# QG-2864KSWEG01_OLED_Display_Module.net
KiCad netlist of a schematic drawn in Altium Designer
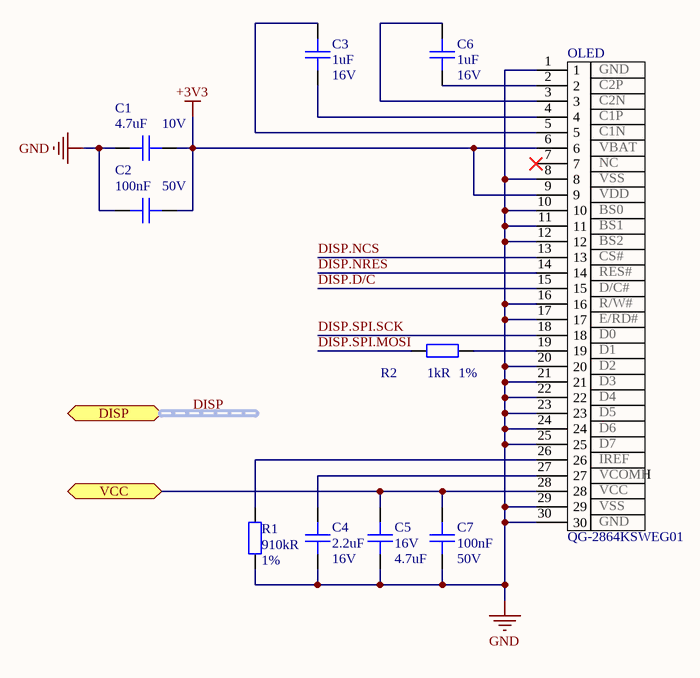
[diagram p0: QG-2864KSWEG01_OLED_Display_Module.SchDoc]

(export (version "E")
  (design (tool "Eeschema 10.0.6"))
  (components
    (comp (ref "C1")
      (value "CAP CER 4.7UF 10V X5R 0603")
      (footprint "C0603")
      (description "4.7µF ±10% 10V Ceramic Capacitor X5R 0603 (1608 Metric)")
      (fields
        (field (name "MANUFACTURER") "Yageo")
        (field (name "MANUFACTURER PART NUMBER") "CC0603KRX5R6BB475")
        (field (name "VOLTAGE RATING") "10V")
        (field (name "CAPACITANCE") "4.7uF")
      )
      (libsource (lib "capacitors_smd") (part "CAP CER 4.7UF 10V X5R 0603"))
    )
    (comp (ref "C2")
      (value "CAP CER 0.1UF 50V X7R 0402")
      (footprint "C0402")
      (description "0.1µF ±10% 50V Ceramic Capacitor X7R 0402 (1005 Metric)")
      (fields
        (field (name "MANUFACTURER PART NUMBER") "CGA2B3X7R1H104K050BB")
        (field (name "MANUFACTURER") "TDK")
        (field (name "CAPACITANCE") "100nF")
        (field (name "VOLTAGE") "50V")
      )
      (libsource (lib "capacitors_smd") (part "CAP CER 0.1UF 50V X7R 0402"))
    )
    (comp (ref "C3")
      (value "CAP CER 1UF 16V X5R 0603")
      (footprint "C0603")
      (description "1µF ±10% 16V Ceramic Capacitor X5R 0603 (1608 Metric)")
      (fields
        (field (name "MANUFACTURER") "Yageo")
        (field (name "MANUFACTURER PART NUMBER") "CC0603KRX5R7BB105")
        (field (name "CAPACITANCE") "1uF")
        (field (name "VOLTAGE RATING") "16V")
      )
      (libsource (lib "capacitors_smd") (part "CAP CER 1UF 16V X5R 0603"))
    )
    (comp (ref "C4")
      (value "CAP CER 2.2UF 16V X5R 0603")
      (footprint "C0603")
      (description "2.2µF ±10% 16V Ceramic Capacitor X5R 0603 (1608 Metric)")
      (fields
        (field (name "MANUFACTURER") "Yageo")
        (field (name "MANUFACTURER PART NUMBER") "CC0603KRX5R7BB225")
        (field (name "CAPACITANCE") "2.2uF")
        (field (name "VOLTAGE RATING") "16V")
      )
      (libsource (lib "capacitors_smd") (part "CAP CER 2.2UF 16V X5R 0603"))
    )
    (comp (ref "C5")
      (value "CAP CER 4.7UF 16V X5R 0603")
      (footprint "C0603")
      (description "4.7µF ±10% 16V Ceramic Capacitor X5R 0603 (1608 Metric)")
      (fields
        (field (name "MANUFACTURER") "Yageo")
        (field (name "MANUFACTURER PART NUMBER") "CC0603KRX5R7BB475")
        (field (name "VOLTAGE RATING") "16V")
        (field (name "CAPACITANCE") "4.7uF")
      )
      (libsource (lib "capacitors_smd") (part "CAP CER 4.7UF 16V X5R 0603"))
    )
    (comp (ref "C6")
      (value "CAP CER 1UF 16V X5R 0603")
      (footprint "C0603")
      (description "1µF ±10% 16V Ceramic Capacitor X5R 0603 (1608 Metric)")
      (fields
        (field (name "MANUFACTURER") "Yageo")
        (field (name "MANUFACTURER PART NUMBER") "CC0603KRX5R7BB105")
        (field (name "CAPACITANCE") "1uF")
        (field (name "VOLTAGE RATING") "16V")
      )
      (libsource (lib "capacitors_smd") (part "CAP CER 1UF 16V X5R 0603"))
    )
    (comp (ref "C7")
      (value "CAP CER 0.1UF 50V X7R 0402")
      (footprint "C0402")
      (description "0.1µF ±10% 50V Ceramic Capacitor X7R 0402 (1005 Metric)")
      (fields
        (field (name "MANUFACTURER PART NUMBER") "CGA2B3X7R1H104K050BB")
        (field (name "MANUFACTURER") "TDK")
        (field (name "CAPACITANCE") "100nF")
        (field (name "VOLTAGE") "50V")
      )
      (libsource (lib "capacitors_smd") (part "CAP CER 0.1UF 50V X7R 0402"))
    )
    (comp (ref "OLED")
      (value "QG-2864KSWEG01")
      (footprint "QG-2864KSWEG01_Flipped")
      (description "OLED Display Module FPC #LT1306P22 TOP 30P 0.7MM")
      (fields
        (field (name "MANUFACTURER") "Limito Technology Inc.")
        (field (name "PIN_1") "GND")
        (field (name "PIN_2") "C2P")
        (field (name "PIN_3") "C2N")
        (field (name "PIN_4") "C1P")
        (field (name "PIN_5") "C1N")
        (field (name "PIN_6") "VBAT")
        (field (name "PIN_7") "NC")
        (field (name "PIN_8") "VSS")
        (field (name "PIN_9") "VDD")
        (field (name "PIN_10") "BS0")
        (field (name "PIN_11") "BS1")
        (field (name "PIN_12") "BS2")
        (field (name "PIN_13") "CS#")
        (field (name "PIN_14") "RES#")
        (field (name "PIN_15") "D/C#")
        (field (name "PIN_16") "R/W#")
        (field (name "PIN_17") "E/RD#")
        (field (name "PIN_18") "D0")
        (field (name "PIN_19") "D1")
        (field (name "PIN_20") "D2")
        (field (name "PIN_21") "D3")
        (field (name "PIN_22") "D4")
        (field (name "PIN_23") "D5")
        (field (name "PIN_24") "D6")
        (field (name "PIN_25") "D7")
        (field (name "PIN_26") "IREF")
        (field (name "PIN_27") "VCOMH")
        (field (name "PIN_28") "VCC")
        (field (name "PIN_29") "VSS")
        (field (name "PIN_30") "GND")
      )
      (libsource (lib "BLDC_Motor_Driver") (part "MOD QG-2864KSWEG01 OLED DISPLAY"))
    )
    (comp (ref "R1")
      (value "RES SMD 910K OHM 1% 1/16W 0402")
      (footprint "R0402")
      (description "910 kOhms ±1% 0.063W, 1/16W Chip Resistor 0402 (1005 Metric) Moisture Resistant Thick Film")
      (fields
        (field (name "MANUFACTURER") "Yageo")
        (field (name "MANUFACTURER PART NUMBER") "RC0402FR-07910KL")
        (field (name "RESISTANCE") "910kR")
        (field (name "TOLERANCE") "1%")
      )
      (libsource (lib "resistors_smd") (part "RES SMD 910K OHM 1% 1/16W 0402"))
    )
    (comp (ref "R2")
      (value "RES SMD 1K OHM 1% 1/16W 0402")
      (footprint "R0402")
      (description "1 kOhms ±1% 0.063W, 1/16W Chip Resistor 0402 (1005 Metric) Moisture Resistant Thick Film")
      (fields
        (field (name "MANUFACTURER") "Yageo")
        (field (name "MANUFACTURER PART NUMBER") "RC0402FR-071KL")
        (field (name "TOLERANCE") "1%")
        (field (name "RESISTANCE") "1kR")
      )
      (libsource (lib "resistors_smd") (part "RES SMD 1K OHM 1% 1/16W 0402"))
    )
  )
  (nets
    (net (code "2") (name "+3V3") (class "Default")
      (node (ref "C1") (pin "1") (pinfunction "1_1") (pintype "passive"))
      (node (ref "C2") (pin "1") (pinfunction "1_1") (pintype "passive"))
      (node (ref "OLED") (pin "6") (pinfunction "6_6") (pintype "passive"))
      (node (ref "OLED") (pin "9") (pinfunction "9_9") (pintype "passive"))
    )
    (net (code "3") (name "/DISP.D{slash}C") (class "Default")
      (node (ref "OLED") (pin "15") (pinfunction "15_15") (pintype "passive"))
    )
    (net (code "4") (name "/DISP.NCS") (class "Default")
      (node (ref "OLED") (pin "13") (pinfunction "13_13") (pintype "passive"))
    )
    (net (code "5") (name "/DISP.NRES") (class "Default")
      (node (ref "OLED") (pin "14") (pinfunction "14_14") (pintype "passive"))
    )
    (net (code "6") (name "/DISP.SPI.MOSI") (class "Default")
      (node (ref "R2") (pin "1") (pinfunction "1_1") (pintype "passive"))
    )
    (net (code "7") (name "/DISP.SPI.SCK") (class "Default")
      (node (ref "OLED") (pin "18") (pinfunction "18_18") (pintype "passive"))
    )
    (net (code "8") (name "/VCC") (class "Default")
      (node (ref "C5") (pin "1") (pinfunction "1_1") (pintype "passive"))
      (node (ref "C7") (pin "1") (pinfunction "1_1") (pintype "passive"))
      (node (ref "OLED") (pin "28") (pinfunction "28_28") (pintype "passive"))
    )
    (net (code "10") (name "GND") (class "Default")
      (node (ref "C1") (pin "2") (pinfunction "2_2") (pintype "passive"))
      (node (ref "C2") (pin "2") (pinfunction "2_2") (pintype "passive"))
      (node (ref "C4") (pin "1") (pinfunction "1_1") (pintype "passive"))
      (node (ref "C5") (pin "2") (pinfunction "2_2") (pintype "passive"))
      (node (ref "C7") (pin "2") (pinfunction "2_2") (pintype "passive"))
      (node (ref "OLED") (pin "1") (pinfunction "1_1") (pintype "passive"))
      (node (ref "OLED") (pin "10") (pinfunction "10_10") (pintype "passive"))
      (node (ref "OLED") (pin "11") (pinfunction "11_11") (pintype "passive"))
      (node (ref "OLED") (pin "12") (pinfunction "12_12") (pintype "passive"))
      (node (ref "OLED") (pin "16") (pinfunction "16_16") (pintype "passive"))
      (node (ref "OLED") (pin "17") (pinfunction "17_17") (pintype "passive"))
      (node (ref "OLED") (pin "20") (pinfunction "20_20") (pintype "passive"))
      (node (ref "OLED") (pin "21") (pinfunction "21_21") (pintype "passive"))
      (node (ref "OLED") (pin "22") (pinfunction "22_22") (pintype "passive"))
      (node (ref "OLED") (pin "23") (pinfunction "23_23") (pintype "passive"))
      (node (ref "OLED") (pin "24") (pinfunction "24_24") (pintype "passive"))
      (node (ref "OLED") (pin "25") (pinfunction "25_25") (pintype "passive"))
      (node (ref "OLED") (pin "29") (pinfunction "29_29") (pintype "passive"))
      (node (ref "OLED") (pin "30") (pinfunction "30_30") (pintype "passive"))
      (node (ref "OLED") (pin "8") (pinfunction "8_8") (pintype "passive"))
      (node (ref "R1") (pin "2") (pinfunction "2_2") (pintype "passive"))
    )
    (net (code "11") (name "Net-(C3-Pad1)") (class "Default")
      (node (ref "C3") (pin "1") (pinfunction "1_1") (pintype "passive"))
      (node (ref "OLED") (pin "4") (pinfunction "4_4") (pintype "passive"))
    )
    (net (code "12") (name "Net-(C3-Pad2)") (class "Default")
      (node (ref "C3") (pin "2") (pinfunction "2_2") (pintype "passive"))
      (node (ref "OLED") (pin "5") (pinfunction "5_5") (pintype "passive"))
    )
    (net (code "13") (name "Net-(C4-Pad2)") (class "Default")
      (node (ref "C4") (pin "2") (pinfunction "2_2") (pintype "passive"))
      (node (ref "OLED") (pin "27") (pinfunction "27_27") (pintype "passive"))
    )
    (net (code "14") (name "Net-(C6-Pad1)") (class "Default")
      (node (ref "C6") (pin "1") (pinfunction "1_1") (pintype "passive"))
      (node (ref "OLED") (pin "2") (pinfunction "2_2") (pintype "passive"))
    )
    (net (code "15") (name "Net-(C6-Pad2)") (class "Default")
      (node (ref "C6") (pin "2") (pinfunction "2_2") (pintype "passive"))
      (node (ref "OLED") (pin "3") (pinfunction "3_3") (pintype "passive"))
    )
    (net (code "16") (name "Net-(OLED-Pad19)") (class "Default")
      (node (ref "OLED") (pin "19") (pinfunction "19_19") (pintype "passive"))
      (node (ref "R2") (pin "2") (pinfunction "2_2") (pintype "passive"))
    )
    (net (code "17") (name "Net-(OLED-Pad26)") (class "Default")
      (node (ref "OLED") (pin "26") (pinfunction "26_26") (pintype "passive"))
      (node (ref "R1") (pin "1") (pinfunction "1_1") (pintype "passive"))
    )
    (net (code "18") (name "unconnected-(OLED-Pad7)") (class "Default")
      (node (ref "OLED") (pin "7") (pinfunction "7_7") (pintype "passive+no_connect"))
    )
  )
)
